# n24.net
KiCad netlist of a schematic drawn in Altium Designer
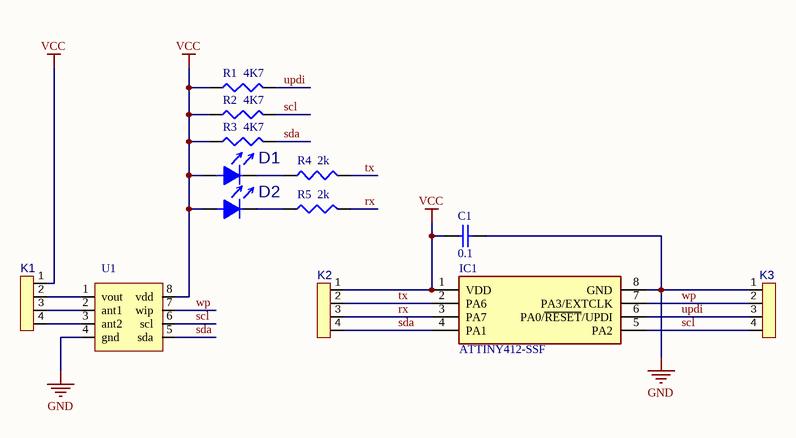
[diagram p0: n24.SchDoc]

(export (version "E")
  (design (tool "Eeschema 10.0.6"))
  (components
    (comp (ref "C1")
      (value "0.1")
      (footprint "SM0805")
      (description "Capacitor")
      (fields (field (name "Comment") "cap0805") (field (name "PUBLISHER") "Altium Limited"))
      (libsource (lib "alt2017") (part "cap0805"))
    )
    (comp (ref "D1")
      (value "LIGHT_SM0805")
      (footprint "SM0805_diode")
      (libsource (lib "alt2017") (part "LIGHT_SM0805"))
    )
    (comp (ref "D2")
      (value "LIGHT_SM0805")
      (footprint "SM0805_diode")
      (libsource (lib "alt2017") (part "LIGHT_SM0805"))
    )
    (comp (ref "IC1")
      (value "ATTINY412-SSF")
      (footprint "SamacSys:SOIC127P600X175-8N")
      (description "Integrated Circuit")
      (fields (field (name "MOUSER PART NUMBER") "579-ATTINY412-SSF"))
      (libsource (lib "*") (part "ATTINY412-SSF"))
    )
    (comp (ref "K1")
      (value "1x4PLS")
      (footprint "4_PLS_2.54")
      (description "1 row 4 pin 2.54mm")
      (libsource (lib "alt2017") (part "1x4PLS"))
    )
    (comp (ref "K2")
      (value "1x4PLS")
      (footprint "4_PLS_2.54")
      (description "1 row 4 pin 2.54mm")
      (libsource (lib "alt2017") (part "1x4PLS"))
    )
    (comp (ref "K3")
      (value "1x4PLS")
      (footprint "4_PLS_2.54")
      (description "1 row 4 pin 2.54mm")
      (libsource (lib "") (part "1x4PLS_1"))
    )
    (comp (ref "R1")
      (value "4K7")
      (footprint "SM0805")
      (description "Resistor")
      (fields (field (name "Comment") "res0805") (field (name "PUBLISHER") "Altium Limited"))
      (libsource (lib "alt2017") (part "res0805"))
    )
    (comp (ref "R2")
      (value "4K7")
      (footprint "SM0805")
      (description "Resistor")
      (fields (field (name "Comment") "res0805") (field (name "PUBLISHER") "Altium Limited"))
      (libsource (lib "alt2017") (part "res0805"))
    )
    (comp (ref "R3")
      (value "4K7")
      (footprint "SM0805")
      (description "Resistor")
      (fields (field (name "Comment") "res0805") (field (name "PUBLISHER") "Altium Limited"))
      (libsource (lib "alt2017") (part "res0805"))
    )
    (comp (ref "R4")
      (value "2k")
      (footprint "SM0805")
      (description "Resistor")
      (fields (field (name "Comment") "res0805") (field (name "PUBLISHER") "Altium Limited"))
      (libsource (lib "alt2017") (part "res0805"))
    )
    (comp (ref "R5")
      (value "2k")
      (footprint "SM0805")
      (description "Resistor")
      (fields (field (name "Comment") "res0805") (field (name "PUBLISHER") "Altium Limited"))
      (libsource (lib "alt2017") (part "res0805"))
    )
    (comp (ref "U1")
      (value "n24rf04")
      (footprint "SO8_L")
      (description "eeprom & nfc tag")
      (libsource (lib "alt2017") (part "n24rf04"))
    )
  )
  (nets
    (net (code "1") (name "/rx") (class "Default")
      (node (ref "IC1") (pin "3") (pinfunction "PA7_3") (pintype "passive"))
      (node (ref "K2") (pin "3") (pinfunction "3_3") (pintype "passive"))
      (node (ref "R5") (pin "2") (pinfunction "2_2") (pintype "passive"))
    )
    (net (code "2") (name "/scl") (class "Default")
      (node (ref "IC1") (pin "5") (pinfunction "PA2_5") (pintype "passive"))
      (node (ref "K3") (pin "4") (pinfunction "4_4") (pintype "passive"))
      (node (ref "R2") (pin "2") (pinfunction "2_2") (pintype "passive"))
      (node (ref "U1") (pin "6") (pinfunction "scl_6") (pintype "passive"))
    )
    (net (code "3") (name "/sda") (class "Default")
      (node (ref "IC1") (pin "4") (pinfunction "PA1_4") (pintype "passive"))
      (node (ref "K2") (pin "4") (pinfunction "4_4") (pintype "passive"))
      (node (ref "R3") (pin "2") (pinfunction "2_2") (pintype "passive"))
      (node (ref "U1") (pin "5") (pinfunction "sda_5") (pintype "passive"))
    )
    (net (code "4") (name "/tx") (class "Default")
      (node (ref "IC1") (pin "2") (pinfunction "PA6_2") (pintype "passive"))
      (node (ref "K2") (pin "2") (pinfunction "2_2") (pintype "passive"))
      (node (ref "R4") (pin "2") (pinfunction "2_2") (pintype "passive"))
    )
    (net (code "5") (name "/updi") (class "Default")
      (node (ref "IC1") (pin "6") (pinfunction "PA0/~{RESET}/UPDI_6") (pintype "passive"))
      (node (ref "K3") (pin "3") (pinfunction "3_3") (pintype "passive"))
      (node (ref "R1") (pin "2") (pinfunction "2_2") (pintype "passive"))
    )
    (net (code "6") (name "/wp") (class "Default")
      (node (ref "IC1") (pin "7") (pinfunction "PA3/EXTCLK_7") (pintype "passive"))
      (node (ref "K3") (pin "2") (pinfunction "2_2") (pintype "passive"))
      (node (ref "U1") (pin "7") (pinfunction "wip_7") (pintype "passive"))
    )
    (net (code "7") (name "GND") (class "Default")
      (node (ref "C1") (pin "2") (pinfunction "2_2") (pintype "passive"))
      (node (ref "IC1") (pin "8") (pinfunction "GND_8") (pintype "passive"))
      (node (ref "K3") (pin "1") (pinfunction "1_1") (pintype "passive"))
      (node (ref "U1") (pin "4") (pinfunction "gnd_4") (pintype "passive"))
    )
    (net (code "8") (name "Net-(D1-k)") (class "Default")
      (node (ref "D1") (pin "2") (pinfunction "k_2") (pintype "passive"))
      (node (ref "R4") (pin "1") (pinfunction "1_1") (pintype "passive"))
    )
    (net (code "9") (name "Net-(D2-k)") (class "Default")
      (node (ref "D2") (pin "2") (pinfunction "k_2") (pintype "passive"))
      (node (ref "R5") (pin "1") (pinfunction "1_1") (pintype "passive"))
    )
    (net (code "10") (name "Net-(U1-ant1)") (class "Default")
      (node (ref "K1") (pin "3") (pinfunction "3_3") (pintype "passive"))
      (node (ref "U1") (pin "2") (pinfunction "ant1_2") (pintype "passive"))
    )
    (net (code "11") (name "Net-(U1-ant2)") (class "Default")
      (node (ref "K1") (pin "4") (pinfunction "4_4") (pintype "passive"))
      (node (ref "U1") (pin "3") (pinfunction "ant2_3") (pintype "passive"))
    )
    (net (code "12") (name "Net-(U1-vout)") (class "Default")
      (node (ref "K1") (pin "2") (pinfunction "2_2") (pintype "passive"))
      (node (ref "U1") (pin "1") (pinfunction "vout_1") (pintype "passive"))
    )
    (net (code "13") (name "VCC") (class "Default")
      (node (ref "C1") (pin "1") (pinfunction "1_1") (pintype "passive"))
      (node (ref "D1") (pin "1") (pinfunction "a_1") (pintype "passive"))
      (node (ref "D2") (pin "1") (pinfunction "a_1") (pintype "passive"))
      (node (ref "IC1") (pin "1") (pinfunction "VDD_1") (pintype "passive"))
      (node (ref "K1") (pin "1") (pinfunction "1_1") (pintype "passive"))
      (node (ref "K2") (pin "1") (pinfunction "1_1") (pintype "passive"))
      (node (ref "R1") (pin "1") (pinfunction "1_1") (pintype "passive"))
      (node (ref "R2") (pin "1") (pinfunction "1_1") (pintype "passive"))
      (node (ref "R3") (pin "1") (pinfunction "1_1") (pintype "passive"))
      (node (ref "U1") (pin "8") (pinfunction "vdd_8") (pintype "passive"))
    )
  )
)
